# C_lula_1.net
KiCad netlist of a schematic drawn in Altium Designer
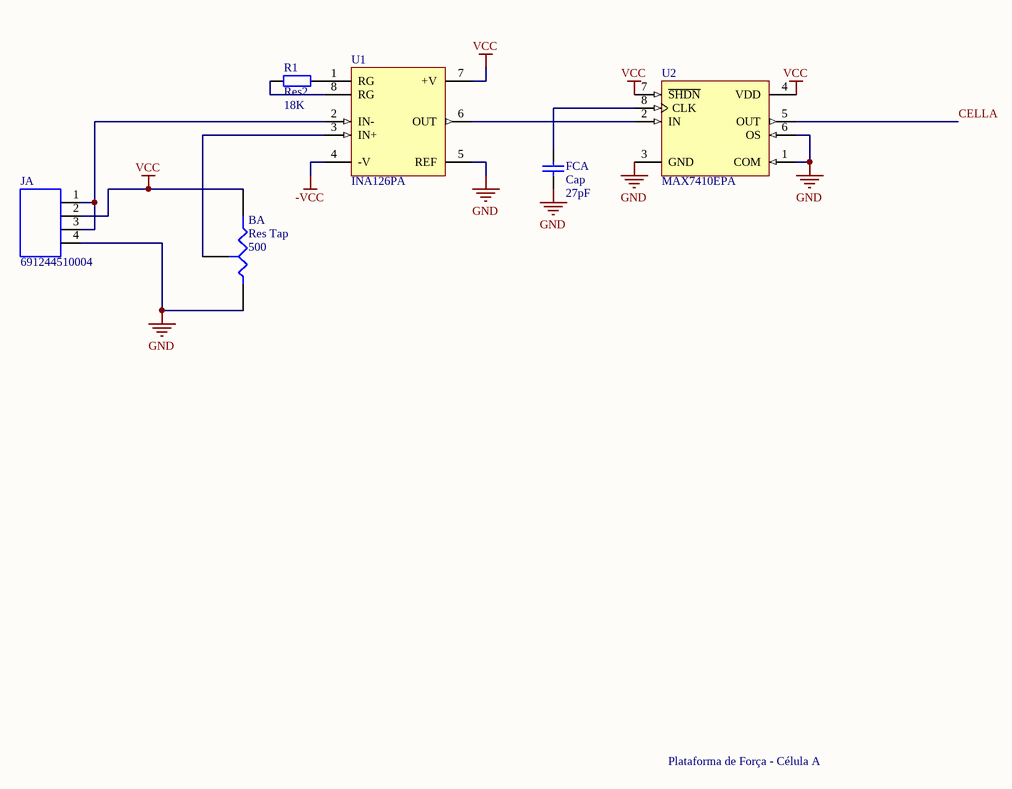
[diagram p0: Célula 1.SchDoc]

(export (version "E")
  (design (tool "Eeschema 10.0.6"))
  (components
    (comp (ref "BA")
      (value "Res Tap")
      (footprint "PcbLib1:TSR3006")
      (description "Tapped Resistor")
      (fields (field (name "ALTIUM_VALUE") "500") (field (name "PUBLISHER") "Altium Limited"))
      (libsource (lib "Miscellaneous Devices") (part "Res Tap"))
    )
    (comp (ref "FCA")
      (value "Cap")
      (footprint "RAD-0.3")
      (description "Capacitor")
      (fields (field (name "ALTIUM_VALUE") "27pF") (field (name "PUBLISHER") "Altium Limited"))
      (libsource (lib "Miscellaneous Devices") (part "Cap"))
    )
    (comp (ref "JA")
      (value "691244510004")
      (footprint "691244510004")
      (description "WR-TBL Horizontal Cable Entry With Rising Cage Clamp,Serie 2445 - 5.08 mm")
      (fields (field (name "MANUFACTURER") "Wurth Elektronik") (field (name "CREATED BY") "Baojun Chen"))
      (libsource (lib "WE_WR-TBL_Rising Cage System_5.08 mm_rev15b") (part "691244510004"))
    )
    (comp (ref "R1")
      (value "Res2")
      (footprint "AXIAL-0.4")
      (description "Resistor")
      (fields (field (name "ALTIUM_VALUE") "18K") (field (name "PUBLISHER") "Altium Limited"))
      (libsource (lib "Miscellaneous Devices") (part "Res2"))
    )
    (comp (ref "U1")
      (value "INA126PA")
      (footprint "006E")
      (description "Precision, Low-Power Instrumentation Amplifiers")
      (fields (field (name "PUBLISHER") "Altium Limited"))
      (libsource (lib "Placa") (part "INA126PA"))
    )
    (comp (ref "U2")
      (value "MAX7410EPA")
      (footprint "PA8")
      (description "5th-Order, Lowpass, Switched-Capacitor Filter")
      (fields (field (name "PUBLISHER") "Altium Limited"))
      (libsource (lib "Maxim Filter Switched Capacitor") (part "MAX7410EPA"))
    )
  )
  (nets
    (net (code "1") (name "-VCC") (class "Default")
      (node (ref "U1") (pin "4") (pinfunction "-V_4") (pintype "power_in"))
    )
    (net (code "2") (name "/CELLA") (class "Default")
      (node (ref "U2") (pin "5") (pinfunction "OUT_5") (pintype "output"))
    )
    (net (code "3") (name "GND") (class "Default")
      (node (ref "BA") (pin "1") (pinfunction "A_1") (pintype "passive"))
      (node (ref "FCA") (pin "1") (pinfunction "1_1") (pintype "passive"))
      (node (ref "JA") (pin "4") (pinfunction "4_4") (pintype "passive"))
      (node (ref "U1") (pin "5") (pinfunction "REF_5") (pintype "passive"))
      (node (ref "U2") (pin "1") (pinfunction "COM_1") (pintype "input"))
      (node (ref "U2") (pin "3") (pinfunction "GND_3") (pintype "power_in"))
      (node (ref "U2") (pin "6") (pinfunction "OS_6") (pintype "input"))
    )
    (net (code "4") (name "Net-(BA-TAP)") (class "Default")
      (node (ref "BA") (pin "3") (pinfunction "TAP_3") (pintype "passive"))
      (node (ref "U1") (pin "3") (pinfunction "IN+_3") (pintype "input"))
    )
    (net (code "5") (name "Net-(R1-Pad1)") (class "Default")
      (node (ref "R1") (pin "1") (pinfunction "1_1") (pintype "passive"))
      (node (ref "U1") (pin "8") (pinfunction "RG_8") (pintype "passive"))
    )
    (net (code "6") (name "Net-(R1-Pad2)") (class "Default")
      (node (ref "R1") (pin "2") (pinfunction "2_2") (pintype "passive"))
      (node (ref "U1") (pin "1") (pinfunction "RG_1") (pintype "passive"))
    )
    (net (code "7") (name "Net-(U1-IN-)") (class "Default")
      (node (ref "JA") (pin "1") (pinfunction "1_1") (pintype "passive"))
      (node (ref "JA") (pin "3") (pinfunction "3_3") (pintype "passive"))
      (node (ref "U1") (pin "2") (pinfunction "IN-_2") (pintype "input"))
    )
    (net (code "8") (name "Net-(U1-OUT)") (class "Default")
      (node (ref "U1") (pin "6") (pinfunction "OUT_6") (pintype "output"))
      (node (ref "U2") (pin "2") (pinfunction "IN_2") (pintype "input"))
    )
    (net (code "9") (name "Net-(U2-CLK)") (class "Default")
      (node (ref "FCA") (pin "2") (pinfunction "2_2") (pintype "passive"))
      (node (ref "U2") (pin "8") (pinfunction "CLK_8") (pintype "input"))
    )
    (net (code "10") (name "VCC") (class "Default")
      (node (ref "BA") (pin "2") (pinfunction "B_2") (pintype "passive"))
      (node (ref "JA") (pin "2") (pinfunction "2_2") (pintype "passive"))
      (node (ref "U1") (pin "7") (pinfunction "+V_7") (pintype "power_in"))
      (node (ref "U2") (pin "4") (pinfunction "VDD_4") (pintype "power_in"))
      (node (ref "U2") (pin "7") (pinfunction "~{SHDN}_7") (pintype "input"))
    )
  )
)
